# MM_2_0_sch.net
KiCad netlist of a schematic drawn in Altium Designer
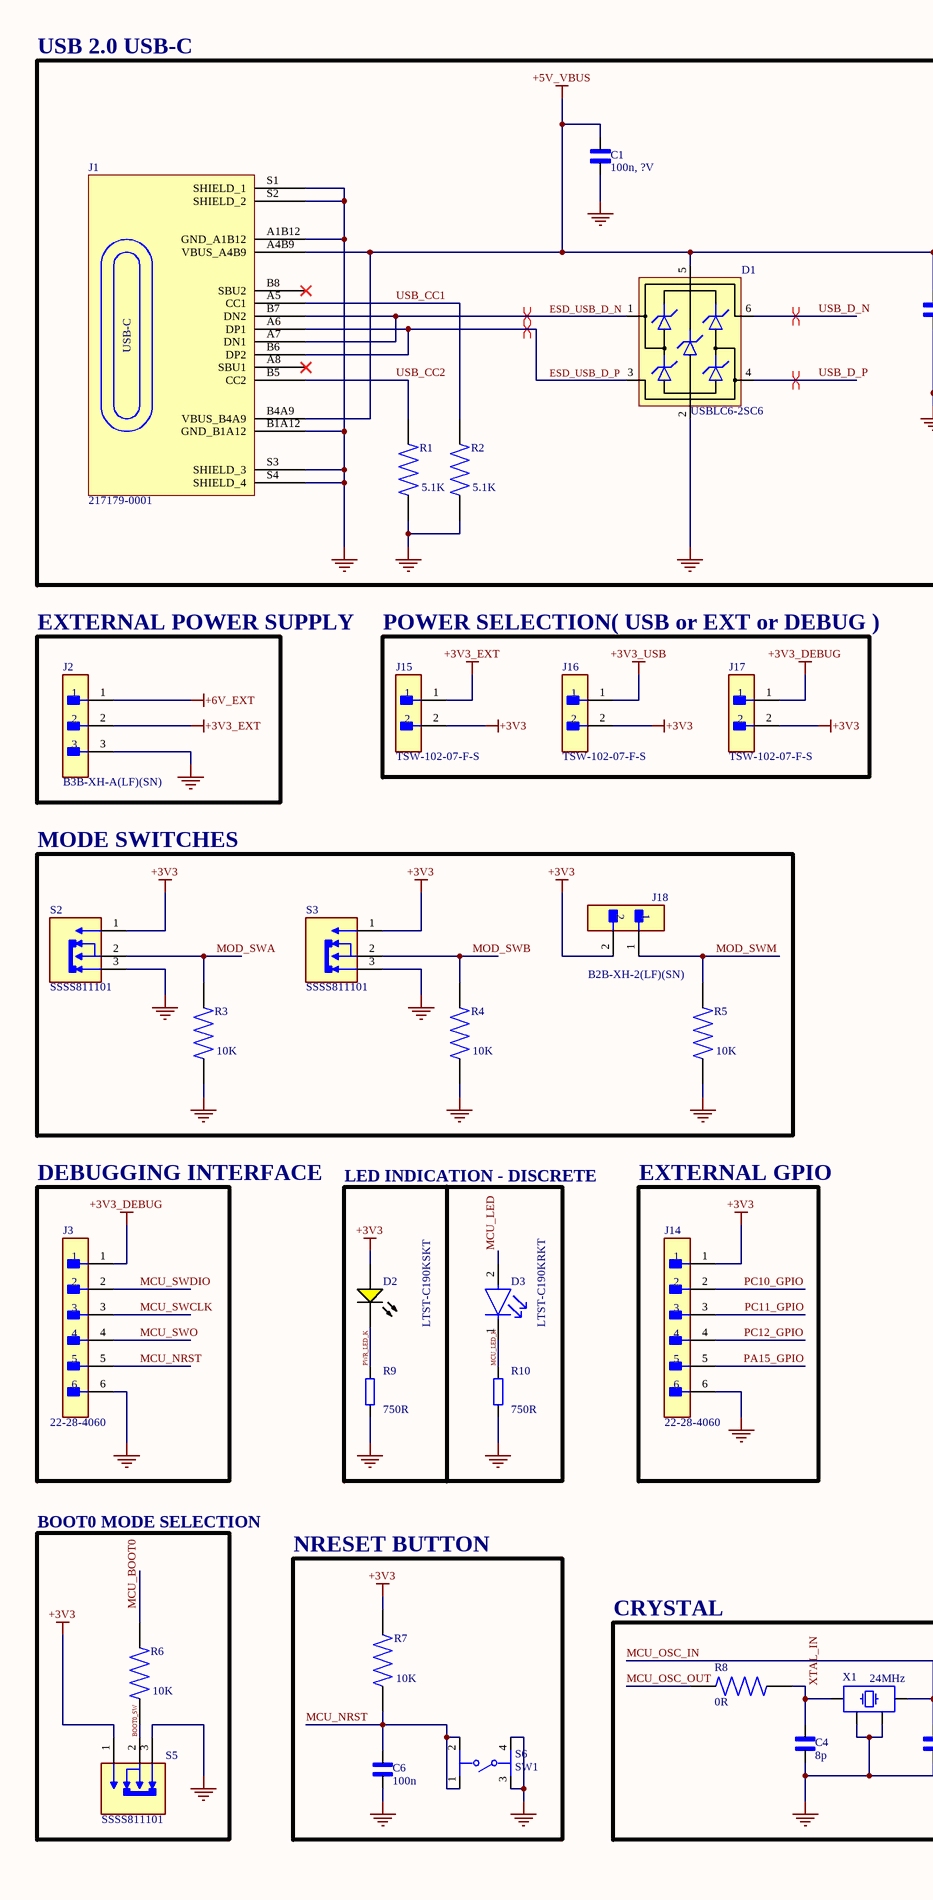
[diagram p0: MM_2.0_sch.SchDoc, left]
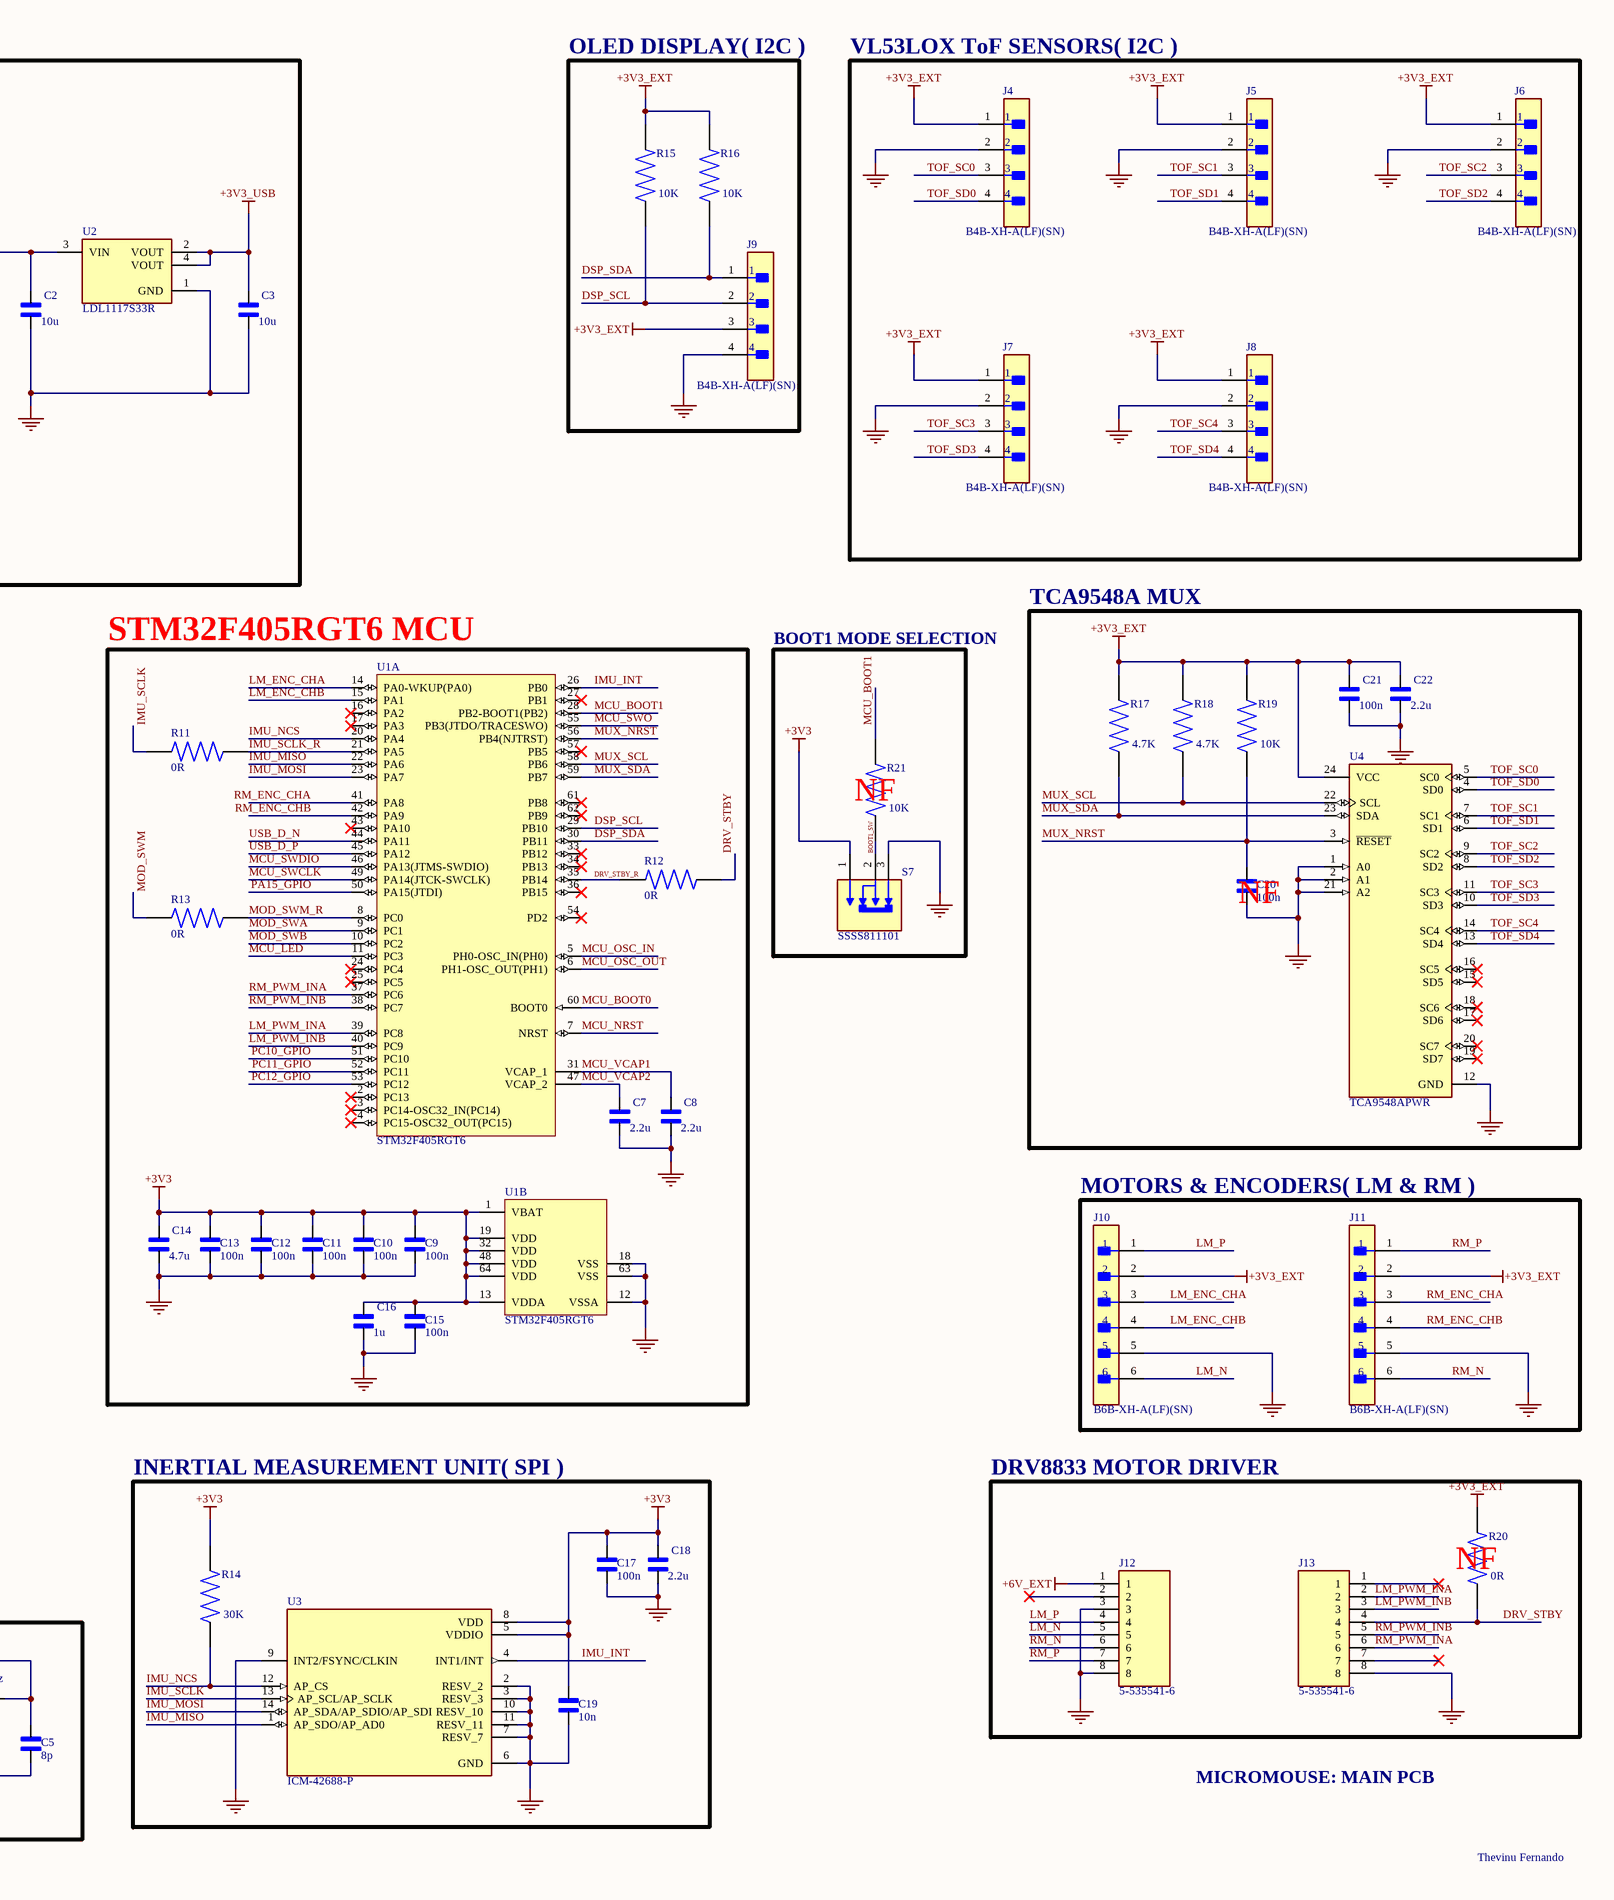
[diagram p1: MM_2.0_sch.SchDoc, right]

(export (version "E")
  (design (tool "Eeschema 10.0.6"))
  (components
    (comp (ref "C1")
      (value "100n, ?V")
      (footprint "CAP_0402")
      (description "0.1 ÂµF Â±10% 16V Ceramic Capacitor X7R 0402 (1005 Metric)")
      (fields (field (name "MF") "Samsung") (field (name "MP") "CL05B104KO5NNNC"))
      (libsource (lib "MM_2.0_schlib") (part "CL05B104KO5NNNC"))
    )
    (comp (ref "C2")
      (value "10u")
      (footprint "CAPC2012X140N")
      (description "10 ÂµF Â±10% 16V Ceramic Capacitor X7R 0805 (2012 Metric)")
      (fields (field (name "MF") "Samsung Electro-Mechanics") (field (name "MP") "CL21B106KOQNNNE"))
      (libsource (lib "MM_2.0_schlib") (part "CL21B106KOQNNNE"))
    )
    (comp (ref "C3")
      (value "10u")
      (footprint "CAPC2012X140N")
      (description "10 ÂµF Â±10% 16V Ceramic Capacitor X7R 0805 (2012 Metric)")
      (fields (field (name "MF") "Samsung Electro-Mechanics") (field (name "MP") "CL21B106KOQNNNE"))
      (libsource (lib "MM_2.0_schlib") (part "CL21B106KOQNNNE"))
    )
    (comp (ref "C4")
      (value "8p")
      (footprint "CAP_0402")
      (description "0.1 ÂµF Â±10% 16V Ceramic Capacitor X7R 0402 (1005 Metric)")
      (fields (field (name "MF") "Samsung") (field (name "MP") "CL05B104KO5NNNC"))
      (libsource (lib "MM_2.0_schlib") (part "CL05B104KO5NNNC"))
    )
    (comp (ref "C5")
      (value "8p")
      (footprint "CAP_0402")
      (description "0.1 ÂµF Â±10% 16V Ceramic Capacitor X7R 0402 (1005 Metric)")
      (fields (field (name "MF") "Samsung") (field (name "MP") "CL05B104KO5NNNC"))
      (libsource (lib "MM_2.0_schlib") (part "CL05B104KO5NNNC"))
    )
    (comp (ref "C6")
      (value "100n")
      (footprint "CAP_0402")
      (description "0.1 ÂµF Â±10% 16V Ceramic Capacitor X7R 0402 (1005 Metric)")
      (fields (field (name "MF") "Samsung") (field (name "MP") "CL05B104KO5NNNC"))
      (libsource (lib "MM_2.0_schlib") (part "CL05B104KO5NNNC"))
    )
    (comp (ref "C7")
      (value "2.2u")
      (footprint "CL10A105KO8NNNC 4.7u 16V 603")
      (description "4.7 ÂµF Â±10% 16V Ceramic Capacitor X5R 0603 (1608 Metric)")
      (fields (field (name "MF") "Samsung Electro-Mechanics") (field (name "MP") "CL10A475KO8NNNC"))
      (libsource (lib "MM_2.0_schlib") (part "CL10A475KO8NNNC"))
    )
    (comp (ref "C8")
      (value "2.2u")
      (footprint "CL10A105KO8NNNC 4.7u 16V 603")
      (description "4.7 ÂµF Â±10% 16V Ceramic Capacitor X5R 0603 (1608 Metric)")
      (fields (field (name "MF") "Samsung Electro-Mechanics") (field (name "MP") "CL10A475KO8NNNC"))
      (libsource (lib "MM_2.0_schlib") (part "CL10A475KO8NNNC"))
    )
    (comp (ref "C9")
      (value "100n")
      (footprint "CAP_0402")
      (description "0.1 ÂµF Â±10% 16V Ceramic Capacitor X7R 0402 (1005 Metric)")
      (fields (field (name "MF") "Samsung") (field (name "MP") "CL05B104KO5NNNC"))
      (libsource (lib "MM_2.0_schlib") (part "CL05B104KO5NNNC"))
    )
    (comp (ref "C10")
      (value "100n")
      (footprint "CAP_0402")
      (description "0.1 ÂµF Â±10% 16V Ceramic Capacitor X7R 0402 (1005 Metric)")
      (fields (field (name "MF") "Samsung") (field (name "MP") "CL05B104KO5NNNC"))
      (libsource (lib "MM_2.0_schlib") (part "CL05B104KO5NNNC"))
    )
    (comp (ref "C11")
      (value "100n")
      (footprint "CAP_0402")
      (description "0.1 ÂµF Â±10% 16V Ceramic Capacitor X7R 0402 (1005 Metric)")
      (fields (field (name "MF") "Samsung") (field (name "MP") "CL05B104KO5NNNC"))
      (libsource (lib "MM_2.0_schlib") (part "CL05B104KO5NNNC"))
    )
    (comp (ref "C12")
      (value "100n")
      (footprint "CAP_0402")
      (description "0.1 ÂµF Â±10% 16V Ceramic Capacitor X7R 0402 (1005 Metric)")
      (fields (field (name "MF") "Samsung") (field (name "MP") "CL05B104KO5NNNC"))
      (libsource (lib "MM_2.0_schlib") (part "CL05B104KO5NNNC"))
    )
    (comp (ref "C13")
      (value "100n")
      (footprint "CAP_0402")
      (description "0.1 ÂµF Â±10% 16V Ceramic Capacitor X7R 0402 (1005 Metric)")
      (fields (field (name "MF") "Samsung") (field (name "MP") "CL05B104KO5NNNC"))
      (libsource (lib "MM_2.0_schlib") (part "CL05B104KO5NNNC"))
    )
    (comp (ref "C14")
      (value "4.7u")
      (footprint "CL10A105KO8NNNC 4.7u 16V 603")
      (description "4.7 ÂµF Â±10% 16V Ceramic Capacitor X5R 0603 (1608 Metric)")
      (fields (field (name "MF") "Samsung Electro-Mechanics") (field (name "MP") "CL10A475KO8NNNC"))
      (libsource (lib "MM_2.0_schlib") (part "CL10A475KO8NNNC"))
    )
    (comp (ref "C15")
      (value "100n")
      (footprint "CAP_0402")
      (description "0.1 ÂµF Â±10% 16V Ceramic Capacitor X7R 0402 (1005 Metric)")
      (fields (field (name "MF") "Samsung") (field (name "MP") "CL05B104KO5NNNC"))
      (libsource (lib "MM_2.0_schlib") (part "CL05B104KO5NNNC"))
    )
    (comp (ref "C16")
      (value "1u")
      (footprint "CL10A105KO8NNNC 1u 16V 603")
      (description "1uF; 16V; X5R; MLCC; Â±10%; SMD; Capacitor: ceramic; 0603; -55Ã·85Â°C")
      (fields (field (name "MF") "Samsung Electro-Mechanics") (field (name "MP") "CL10A105KO8NNNC"))
      (libsource (lib "MM_2.0_schlib") (part "CL10A105KO8NNNC"))
    )
    (comp (ref "C17")
      (value "100n")
      (footprint "CAP_0402")
      (description "0.1 ÂµF Â±10% 16V Ceramic Capacitor X7R 0402 (1005 Metric)")
      (fields (field (name "MF") "Samsung") (field (name "MP") "CL05B104KO5NNNC"))
      (libsource (lib "MM_2.0_schlib") (part "CL05B104KO5NNNC"))
    )
    (comp (ref "C18")
      (value "2.2u")
      (footprint "CL10A105KO8NNNC 4.7u 16V 603")
      (description "4.7 ÂµF Â±10% 16V Ceramic Capacitor X5R 0603 (1608 Metric)")
      (fields (field (name "MF") "Samsung Electro-Mechanics") (field (name "MP") "CL10A475KO8NNNC"))
      (libsource (lib "MM_2.0_schlib") (part "CL10A475KO8NNNC"))
    )
    (comp (ref "C19")
      (value "10n")
      (footprint "CAP_0402")
      (description "0.1 ÂµF Â±10% 16V Ceramic Capacitor X7R 0402 (1005 Metric)")
      (fields (field (name "MF") "Samsung") (field (name "MP") "CL05B104KO5NNNC"))
      (libsource (lib "MM_2.0_schlib") (part "CL05B104KO5NNNC"))
    )
    (comp (ref "C20")
      (value "100n")
      (footprint "CAP_0402")
      (description "0.1 ÂµF Â±10% 16V Ceramic Capacitor X7R 0402 (1005 Metric)")
      (fields (field (name "MF") "Samsung") (field (name "MP") "CL05B104KO5NNNC"))
      (libsource (lib "MM_2.0_schlib") (part "CL05B104KO5NNNC"))
    )
    (comp (ref "C21")
      (value "100n")
      (footprint "CAP_0402")
      (description "0.1 ÂµF Â±10% 16V Ceramic Capacitor X7R 0402 (1005 Metric)")
      (fields (field (name "MF") "Samsung") (field (name "MP") "CL05B104KO5NNNC"))
      (libsource (lib "MM_2.0_schlib") (part "CL05B104KO5NNNC"))
    )
    (comp (ref "C22")
      (value "2.2u")
      (footprint "CL10A105KO8NNNC 4.7u 16V 603")
      (description "4.7 ÂµF Â±10% 16V Ceramic Capacitor X5R 0603 (1608 Metric)")
      (fields (field (name "MF") "Samsung Electro-Mechanics") (field (name "MP") "CL10A475KO8NNNC"))
      (libsource (lib "MM_2.0_schlib") (part "CL10A475KO8NNNC"))
    )
    (comp (ref "D1")
      (value "USBLC6-2SC6")
      (footprint "SOT95P280X145-6N")
      (description "Low-Capacitance ESD Protection USB")
      (fields (field (name "MANUFACTURER") "STMicroelectronics"))
      (libsource (lib "MM_2.0_schlib") (part "USBLC6-2SC6"))
    )
    (comp (ref "D2")
      (value "LTST-C190KSKT")
      (footprint "LTST-C190KSKT_V")
      (description "LED Uni-Color Yellow, 75 mW, 30 mA, -30 to 85 degC, 2-Pin SMD, RoHS, Tape and Reel")
      (fields (field (name "TOLERANCE") "1%"))
      (libsource (lib "MM_2.0_schlib") (part "CMP-1674-00009-1"))
    )
    (comp (ref "D3")
      (value "LTST-C190KRKT")
      (footprint "FP-LTST-C190KRKT-MFG")
      (description "LED RED CLEAR CHIP SMD")
      (libsource (lib "MM_2.0_schlib") (part "CMP-1674-00011-2"))
    )
    (comp (ref "J1")
      (value "217179-0001")
      (footprint "FP-2171790001-MFG USB-C 2.0")
      (description "CONN RCP USB2.0 TYP C 24P SMD RA")
      (fields (field (name "MANUFACTURER") "Molex") (field (name "LCSC PART NUMBER") "C3197684"))
      (libsource (lib "MM_2.0_schlib") (part "217179-0001"))
    )
    (comp (ref "J2")
      (value "B3B-XH-A(LF)(SN)")
      (footprint "FP-B3B-XH-A_LF_SN-MFG")
      (description "CONN HEADER VERT 3POS 2.5MM")
      (libsource (lib "MM_2.0_schlib") (part "CMP-17439-000014-3"))
    )
    (comp (ref "J3")
      (value "22-28-4060")
      (footprint "FP-22-28-4060-MFG")
      (description "CONN HEADER VERT 6POS 2.54MM")
      (libsource (lib "MM_2.0_schlib") (part "f2cb566baf1c37ab5a3b8e90bbeafd6"))
    )
    (comp (ref "J4")
      (value "B4B-XH-A(LF)(SN)")
      (footprint "FP-B4B-XH-A_LF_SN-MFG")
      (description "CONN HEADER VERT 4POS 2.5MM")
      (libsource (lib "MM_2.0_schlib") (part "CMP-17439-000250-1"))
    )
    (comp (ref "J5")
      (value "B4B-XH-A(LF)(SN)")
      (footprint "FP-B4B-XH-A_LF_SN-MFG")
      (description "CONN HEADER VERT 4POS 2.5MM")
      (libsource (lib "MM_2.0_schlib") (part "CMP-17439-000250-1"))
    )
    (comp (ref "J6")
      (value "B4B-XH-A(LF)(SN)")
      (footprint "FP-B4B-XH-A_LF_SN-MFG")
      (description "CONN HEADER VERT 4POS 2.5MM")
      (libsource (lib "MM_2.0_schlib") (part "CMP-17439-000250-1"))
    )
    (comp (ref "J7")
      (value "B4B-XH-A(LF)(SN)")
      (footprint "FP-B4B-XH-A_LF_SN-MFG")
      (description "CONN HEADER VERT 4POS 2.5MM")
      (libsource (lib "MM_2.0_schlib") (part "CMP-17439-000250-1"))
    )
    (comp (ref "J8")
      (value "B4B-XH-A(LF)(SN)")
      (footprint "FP-B4B-XH-A_LF_SN-MFG")
      (description "CONN HEADER VERT 4POS 2.5MM")
      (libsource (lib "MM_2.0_schlib") (part "CMP-17439-000250-1"))
    )
    (comp (ref "J9")
      (value "B4B-XH-A(LF)(SN)")
      (footprint "FP-B4B-XH-A_LF_SN-MFG")
      (description "CONN HEADER VERT 4POS 2.5MM")
      (libsource (lib "MM_2.0_schlib") (part "CMP-17439-000250-1"))
    )
    (comp (ref "J10")
      (value "B6B-XH-A(LF)(SN)")
      (footprint "FP-B6B-XH-A_LF_SN-MFG")
      (description "CONN HEADER VERT 6POS 2.5MM")
      (libsource (lib "MM_2.0_schlib") (part "CMP-17439-000076-1"))
    )
    (comp (ref "J11")
      (value "B6B-XH-A(LF)(SN)")
      (footprint "FP-B6B-XH-A_LF_SN-MFG")
      (description "CONN HEADER VERT 6POS 2.5MM")
      (libsource (lib "MM_2.0_schlib") (part "CMP-17439-000076-1"))
    )
    (comp (ref "J12")
      (value "5-535541-6")
      (footprint "TE_5-535541-6")
      (fields (field (name "MF") "TE Connectivity"))
      (libsource (lib "") (part "5-535541-6_1"))
    )
    (comp (ref "J13")
      (value "5-535541-6")
      (footprint "TE_5-535541-6")
      (fields (field (name "MF") "TE Connectivity"))
      (libsource (lib "MM_2.0_schlib") (part "5-535541-6"))
    )
    (comp (ref "J14")
      (value "22-28-4060")
      (footprint "FP-22-28-4060-MFG")
      (description "CONN HEADER VERT 6POS 2.54MM")
      (libsource (lib "MM_2.0_schlib") (part "f2cb566baf1c37ab5a3b8e90bbeafd6"))
    )
    (comp (ref "J15")
      (value "TSW-102-07-F-S")
      (footprint "FP-TSW-102-07-F-S-MFG")
      (description "CONN HEADER VERT 2POS 2.54MM")
      (libsource (lib "MM_2.0_schlib") (part "CMP-02766-001458-1"))
    )
    (comp (ref "J16")
      (value "TSW-102-07-F-S")
      (footprint "FP-TSW-102-07-F-S-MFG")
      (description "CONN HEADER VERT 2POS 2.54MM")
      (libsource (lib "MM_2.0_schlib") (part "CMP-02766-001458-1"))
    )
    (comp (ref "J17")
      (value "TSW-102-07-F-S")
      (footprint "FP-TSW-102-07-F-S-MFG")
      (description "CONN HEADER VERT 2POS 2.54MM")
      (libsource (lib "MM_2.0_schlib") (part "CMP-02766-001458-1"))
    )
    (comp (ref "J18")
      (value "B2B-XH-2(LF)(SN)")
      (footprint "FP-B2B-XH-2_LF_SN-MFG")
      (description "CONN HEADER VERT 2POS 2.5MM")
      (libsource (lib "MM_2.0_schlib") (part "CMP-17439-000499-1"))
    )
    (comp (ref "R1")
      (value "5.1K")
      (footprint "RES_ERJ2RKF1002X 100K 100mW 402")
      (description "10 kOhms 1% 0.1W, 1/10W Chip Resistor 0402 (1005 Metric) Automotive AEC-Q200 Thick Film")
      (fields (field (name "MF") "Panasonic") (field (name "MP") "ERJ-2RKF1002X"))
      (libsource (lib "MM_2.0_schlib") (part "ERJ2RKF1002X"))
    )
    (comp (ref "R2")
      (value "5.1K")
      (footprint "RES_ERJ2RKF1002X 100K 100mW 402")
      (description "10 kOhms 1% 0.1W, 1/10W Chip Resistor 0402 (1005 Metric) Automotive AEC-Q200 Thick Film")
      (fields (field (name "MF") "Panasonic") (field (name "MP") "ERJ-2RKF1002X"))
      (libsource (lib "MM_2.0_schlib") (part "ERJ2RKF1002X"))
    )
    (comp (ref "R3")
      (value "10K")
      (footprint "RES_ERJ2RKF1002X 100K 100mW 402")
      (description "10 kOhms 1% 0.1W, 1/10W Chip Resistor 0402 (1005 Metric) Automotive AEC-Q200 Thick Film")
      (fields (field (name "MF") "Panasonic") (field (name "MP") "ERJ-2RKF1002X"))
      (libsource (lib "MM_2.0_schlib") (part "ERJ2RKF1002X"))
    )
    (comp (ref "R4")
      (value "10K")
      (footprint "RES_ERJ2RKF1002X 100K 100mW 402")
      (description "10 kOhms 1% 0.1W, 1/10W Chip Resistor 0402 (1005 Metric) Automotive AEC-Q200 Thick Film")
      (fields (field (name "MF") "Panasonic") (field (name "MP") "ERJ-2RKF1002X"))
      (libsource (lib "MM_2.0_schlib") (part "ERJ2RKF1002X"))
    )
    (comp (ref "R5")
      (value "10K")
      (footprint "RES_ERJ2RKF1002X 100K 100mW 402")
      (description "10 kOhms 1% 0.1W, 1/10W Chip Resistor 0402 (1005 Metric) Automotive AEC-Q200 Thick Film")
      (fields (field (name "MF") "Panasonic") (field (name "MP") "ERJ-2RKF1002X"))
      (libsource (lib "MM_2.0_schlib") (part "ERJ2RKF1002X"))
    )
    (comp (ref "R6")
      (value "10K")
      (footprint "RES_ERJ2RKF1002X 100K 100mW 402")
      (description "10 kOhms 1% 0.1W, 1/10W Chip Resistor 0402 (1005 Metric) Automotive AEC-Q200 Thick Film")
      (fields (field (name "MF") "Panasonic") (field (name "MP") "ERJ-2RKF1002X"))
      (libsource (lib "MM_2.0_schlib") (part "ERJ2RKF1002X"))
    )
    (comp (ref "R7")
      (value "10K")
      (footprint "RES_ERJ2RKF1002X 100K 100mW 402")
      (description "10 kOhms 1% 0.1W, 1/10W Chip Resistor 0402 (1005 Metric) Automotive AEC-Q200 Thick Film")
      (fields (field (name "MF") "Panasonic") (field (name "MP") "ERJ-2RKF1002X"))
      (libsource (lib "MM_2.0_schlib") (part "ERJ2RKF1002X"))
    )
    (comp (ref "R8")
      (value "0R")
      (footprint "RES_ERJ2RKF1002X 100K 100mW 402")
      (description "10 kOhms 1% 0.1W, 1/10W Chip Resistor 0402 (1005 Metric) Automotive AEC-Q200 Thick Film")
      (fields (field (name "MF") "Panasonic") (field (name "MP") "ERJ-2RKF1002X"))
      (libsource (lib "MM_2.0_schlib") (part "ERJ2RKF1002X"))
    )
    (comp (ref "R9")
      (value "750R")
      (footprint "RES_0603")
      (description "Resistor SMD 0603")
      (libsource (lib "MM_2.0_schlib") (part "RES_0603"))
    )
    (comp (ref "R10")
      (value "750R")
      (footprint "RES_0603")
      (description "Resistor SMD 0603")
      (libsource (lib "MM_2.0_schlib") (part "RES_0603"))
    )
    (comp (ref "R11")
      (value "0R")
      (footprint "RES_ERJ2RKF1002X 100K 100mW 402")
      (description "10 kOhms 1% 0.1W, 1/10W Chip Resistor 0402 (1005 Metric) Automotive AEC-Q200 Thick Film")
      (fields (field (name "MF") "Panasonic") (field (name "MP") "ERJ-2RKF1002X"))
      (libsource (lib "MM_2.0_schlib") (part "ERJ2RKF1002X"))
    )
    (comp (ref "R12")
      (value "0R")
      (footprint "RES_ERJ2RKF1002X 100K 100mW 402")
      (description "10 kOhms 1% 0.1W, 1/10W Chip Resistor 0402 (1005 Metric) Automotive AEC-Q200 Thick Film")
      (fields (field (name "MF") "Panasonic") (field (name "MP") "ERJ-2RKF1002X"))
      (libsource (lib "MM_2.0_schlib") (part "ERJ2RKF1002X"))
    )
    (comp (ref "R13")
      (value "0R")
      (footprint "RES_ERJ2RKF1002X 100K 100mW 402")
      (description "10 kOhms 1% 0.1W, 1/10W Chip Resistor 0402 (1005 Metric) Automotive AEC-Q200 Thick Film")
      (fields (field (name "MF") "Panasonic") (field (name "MP") "ERJ-2RKF1002X"))
      (libsource (lib "MM_2.0_schlib") (part "ERJ2RKF1002X"))
    )
    (comp (ref "R14")
      (value "30K")
      (footprint "RES_ERJ2RKF1002X 100K 100mW 402")
      (description "10 kOhms 1% 0.1W, 1/10W Chip Resistor 0402 (1005 Metric) Automotive AEC-Q200 Thick Film")
      (fields (field (name "MF") "Panasonic") (field (name "MP") "ERJ-2RKF1002X"))
      (libsource (lib "MM_2.0_schlib") (part "ERJ2RKF1002X"))
    )
    (comp (ref "R15")
      (value "10K")
      (footprint "RES_ERJ2RKF1002X 100K 100mW 402")
      (description "10 kOhms 1% 0.1W, 1/10W Chip Resistor 0402 (1005 Metric) Automotive AEC-Q200 Thick Film")
      (fields (field (name "MF") "Panasonic") (field (name "MP") "ERJ-2RKF1002X"))
      (libsource (lib "MM_2.0_schlib") (part "ERJ2RKF1002X"))
    )
    (comp (ref "R16")
      (value "10K")
      (footprint "RES_ERJ2RKF1002X 100K 100mW 402")
      (description "10 kOhms 1% 0.1W, 1/10W Chip Resistor 0402 (1005 Metric) Automotive AEC-Q200 Thick Film")
      (fields (field (name "MF") "Panasonic") (field (name "MP") "ERJ-2RKF1002X"))
      (libsource (lib "MM_2.0_schlib") (part "ERJ2RKF1002X"))
    )
    (comp (ref "R17")
      (value "4.7K")
      (footprint "RES_ERJ2RKF1002X 100K 100mW 402")
      (description "10 kOhms 1% 0.1W, 1/10W Chip Resistor 0402 (1005 Metric) Automotive AEC-Q200 Thick Film")
      (fields (field (name "MF") "Panasonic") (field (name "MP") "ERJ-2RKF1002X"))
      (libsource (lib "MM_2.0_schlib") (part "ERJ2RKF1002X"))
    )
    (comp (ref "R18")
      (value "4.7K")
      (footprint "RES_ERJ2RKF1002X 100K 100mW 402")
      (description "10 kOhms 1% 0.1W, 1/10W Chip Resistor 0402 (1005 Metric) Automotive AEC-Q200 Thick Film")
      (fields (field (name "MF") "Panasonic") (field (name "MP") "ERJ-2RKF1002X"))
      (libsource (lib "MM_2.0_schlib") (part "ERJ2RKF1002X"))
    )
    (comp (ref "R19")
      (value "10K")
      (footprint "RES_ERJ2RKF1002X 100K 100mW 402")
      (description "10 kOhms 1% 0.1W, 1/10W Chip Resistor 0402 (1005 Metric) Automotive AEC-Q200 Thick Film")
      (fields (field (name "MF") "Panasonic") (field (name "MP") "ERJ-2RKF1002X"))
      (libsource (lib "MM_2.0_schlib") (part "ERJ2RKF1002X"))
    )
    (comp (ref "R20")
      (value "0R")
      (footprint "RES_ERJ2RKF1002X 100K 100mW 402")
      (description "10 kOhms 1% 0.1W, 1/10W Chip Resistor 0402 (1005 Metric) Automotive AEC-Q200 Thick Film")
      (fields (field (name "MF") "Panasonic") (field (name "MP") "ERJ-2RKF1002X"))
      (libsource (lib "MM_2.0_schlib") (part "ERJ2RKF1002X"))
    )
    (comp (ref "R21")
      (value "10K")
      (footprint "RES_ERJ2RKF1002X 100K 100mW 402")
      (description "10 kOhms 1% 0.1W, 1/10W Chip Resistor 0402 (1005 Metric) Automotive AEC-Q200 Thick Film")
      (fields (field (name "MF") "Panasonic") (field (name "MP") "ERJ-2RKF1002X"))
      (libsource (lib "MM_2.0_schlib") (part "ERJ2RKF1002X"))
    )
    (comp (ref "S2")
      (value "SSSS811101")
      (footprint "SW_SSSS811101")
      (description "Switch Slide SP Side Slide 0.3A 5VDC 10000Cycles Gull Wing SMD T/R")
      (fields (field (name "MF") "ALPS"))
      (libsource (lib "MM_2.0_schlib") (part "SSSS811101"))
    )
    (comp (ref "S3")
      (value "SSSS811101")
      (footprint "SW_SSSS811101")
      (description "Switch Slide SP Side Slide 0.3A 5VDC 10000Cycles Gull Wing SMD T/R")
      (fields (field (name "MF") "ALPS"))
      (libsource (lib "MM_2.0_schlib") (part "SSSS811101"))
    )
    (comp (ref "S5")
      (value "SSSS811101")
      (footprint "SW_SSSS811101")
      (description "Switch Slide SP Side Slide 0.3A 5VDC 10000Cycles Gull Wing SMD T/R")
      (fields (field (name "MF") "ALPS"))
      (libsource (lib "") (part "SSSS811101_1"))
    )
    (comp (ref "S6")
      (value "SW1")
      (footprint "FP-PTS645SM43SMTR92LFS-MFG")
      (description "SWITCH TACTILE SPST-NO 0.05A 12V")
      (libsource (lib "MM_2.0_schlib") (part "PTS645SM43SMTR92LFS"))
    )
    (comp (ref "S7")
      (value "SSSS811101")
      (footprint "SW_SSSS811101")
      (description "Switch Slide SP Side Slide 0.3A 5VDC 10000Cycles Gull Wing SMD T/R")
      (fields (field (name "MF") "ALPS"))
      (libsource (lib "") (part "SSSS811101_1"))
    )
    (comp (ref "U1")
      (value "STM32F405RGT6")
      (footprint "STM-LQFP64_L")
      (fields (field (name "MANUFACTURER") "STMicroelectronics"))
      (libsource (lib "Altium Content Vault") (part "MC-ARM-STM32F4X5-SQ64"))
    )
    (comp (ref "U2")
      (value "LDL1117S33R")
      (footprint "FP-SOT223-0046067-IPC_A")
      (description "IC REG LINEAR 3.3V 1.2A SOT223")
      (fields
        (field (name "OCTOPART") "https://octopart.com/ldl1117s33r-stmicroelectronics-81876163")
        (field (name "MANUFACTURER") "STMicroelectronics")
      )
      (libsource (lib "MM_2.0_schlib") (part "CMP-12153-000006-1"))
    )
    (comp (ref "U3")
      (value "ICM-42688-P")
      (footprint "PQFN50P300X250X97-14N")
      (description "Accelerometer, Gyroscope, 6 Axis Sensor Output")
      (libsource (lib "MM_2.0_schlib") (part "ICM-42688-P"))
    )
    (comp (ref "U4")
      (value "TCA9548APWR")
      (footprint "FP-PW0024A-IPC_A")
      (description "IC I2C SW 8CH W/RESET 24TSSOP")
      (fields
        (field (name "MANUFACTURER") "Texas Instruments")
        (field (name "OCTOPART") "https://octopart.com/tca9548apwr-texas+instruments-22266789")
      )
      (libsource (lib "MM_2.0_schlib") (part "CMP-04892-000002-1"))
    )
    (comp (ref "X1")
      (value "24MHz")
      (footprint "XTAL_3225")
      (description "Crystal SMD 24MHz 10PPM 7pF 3225")
      (fields
        (field (name "MANUFACTURER") "Epson")
        (field (name "MANUFACTURER PART NUMBER") "TSX-3225 24.0000MF15X-AC")
      )
      (libsource (lib "MM_2.0_schlib") (part "TSX-3225_24.0000MF15X-AC"))
    )
  )
  (nets
    (net (code "1") (name "+3V3") (class "Default")
      (node (ref "C10") (pin "2") (pinfunction "2_2") (pintype "passive"))
      (node (ref "C11") (pin "2") (pinfunction "2_2") (pintype "passive"))
      (node (ref "C12") (pin "2") (pinfunction "2_2") (pintype "passive"))
      (node (ref "C13") (pin "2") (pinfunction "2_2") (pintype "passive"))
      (node (ref "C14") (pin "1") (pinfunction "1_1") (pintype "passive"))
      (node (ref "C15") (pin "2") (pinfunction "2_2") (pintype "passive"))
      (node (ref "C16") (pin "1") (pinfunction "1_1") (pintype "passive"))
      (node (ref "C17") (pin "2") (pinfunction "2_2") (pintype "passive"))
      (node (ref "C18") (pin "1") (pinfunction "1_1") (pintype "passive"))
      (node (ref "C19") (pin "2") (pinfunction "2_2") (pintype "passive"))
      (node (ref "C9") (pin "2") (pinfunction "2_2") (pintype "passive"))
      (node (ref "D2") (pin "1") (pinfunction "A_1") (pintype "passive"))
      (node (ref "J14") (pin "1") (pinfunction "1_1") (pintype "passive"))
      (node (ref "J15") (pin "2") (pinfunction "2_2") (pintype "passive"))
      (node (ref "J16") (pin "2") (pinfunction "2_2") (pintype "passive"))
      (node (ref "J17") (pin "2") (pinfunction "2_2") (pintype "passive"))
      (node (ref "J18") (pin "2") (pinfunction "2_2") (pintype "passive"))
      (node (ref "R14") (pin "2") (pinfunction "2_2") (pintype "passive"))
      (node (ref "R7") (pin "2") (pinfunction "2_2") (pintype "passive"))
      (node (ref "S2") (pin "1") (pinfunction "1_1") (pintype "passive"))
      (node (ref "S3") (pin "1") (pinfunction "1_1") (pintype "passive"))
      (node (ref "S5") (pin "1") (pinfunction "1_1") (pintype "passive"))
      (node (ref "S7") (pin "1") (pinfunction "1_1") (pintype "passive"))
      (node (ref "U1") (pin "1") (pinfunction "VBAT_1") (pintype "power_in"))
      (node (ref "U1") (pin "13") (pinfunction "VDDA_13") (pintype "power_in"))
      (node (ref "U1") (pin "19") (pinfunction "VDD_19") (pintype "power_in"))
      (node (ref "U1") (pin "32") (pinfunction "VDD_32") (pintype "power_in"))
      (node (ref "U1") (pin "48") (pinfunction "VDD_48") (pintype "power_in"))
      (node (ref "U1") (pin "64") (pinfunction "VDD_64") (pintype "power_in"))
      (node (ref "U3") (pin "5") (pinfunction "VDDIO_5") (pintype "power_in"))
      (node (ref "U3") (pin "8") (pinfunction "VDD_8") (pintype "power_in"))
    )
    (net (code "2") (name "+3V3_DEBUG") (class "Default")
      (node (ref "J17") (pin "1") (pinfunction "1_1") (pintype "passive"))
      (node (ref "J3") (pin "1") (pinfunction "1_1") (pintype "passive"))
    )
    (net (code "3") (name "+3V3_EXT") (class "Default")
      (node (ref "C21") (pin "2") (pinfunction "2_2") (pintype "passive"))
      (node (ref "C22") (pin "1") (pinfunction "1_1") (pintype "passive"))
      (node (ref "J10") (pin "2") (pinfunction "2_2") (pintype "passive"))
      (node (ref "J11") (pin "2") (pinfunction "2_2") (pintype "passive"))
      (node (ref "J15") (pin "1") (pinfunction "1_1") (pintype "passive"))
      (node (ref "J2") (pin "2") (pinfunction "2_2") (pintype "passive"))
      (node (ref "J4") (pin "1") (pinfunction "1_1") (pintype "passive"))
      (node (ref "J5") (pin "1") (pinfunction "1_1") (pintype "passive"))
      (node (ref "J6") (pin "1") (pinfunction "1_1") (pintype "passive"))
      (node (ref "J7") (pin "1") (pinfunction "1_1") (pintype "passive"))
      (node (ref "J8") (pin "1") (pinfunction "1_1") (pintype "passive"))
      (node (ref "J9") (pin "3") (pinfunction "3_3") (pintype "passive"))
      (node (ref "R15") (pin "2") (pinfunction "2_2") (pintype "passive"))
      (node (ref "R16") (pin "2") (pinfunction "2_2") (pintype "passive"))
      (node (ref "R17") (pin "2") (pinfunction "2_2") (pintype "passive"))
      (node (ref "R18") (pin "2") (pinfunction "2_2") (pintype "passive"))
      (node (ref "R19") (pin "2") (pinfunction "2_2") (pintype "passive"))
      (node (ref "R20") (pin "2") (pinfunction "2_2") (pintype "passive"))
      (node (ref "U4") (pin "24") (pinfunction "VCC_24") (pintype "power_in"))
    )
    (net (code "4") (name "+3V3_USB") (class "Default")
      (node (ref "C3") (pin "1") (pinfunction "1_1") (pintype "passive"))
      (node (ref "J16") (pin "1") (pinfunction "1_1") (pintype "passive"))
      (node (ref "U2") (pin "2") (pinfunction "VOUT_2") (pintype "power_in"))
      (node (ref "U2") (pin "4") (pinfunction "VOUT_4") (pintype "power_in"))
    )
    (net (code "5") (name "+5V_VBUS") (class "Default")
      (node (ref "C1") (pin "2") (pinfunction "2_2") (pintype "passive"))
      (node (ref "C2") (pin "1") (pinfunction "1_1") (pintype "passive"))
      (node (ref "D1") (pin "5") (pinfunction "VBUS_5") (pintype "power_in"))
      (node (ref "J1") (pin "A4B9") (pinfunction "VBUS_A4B9_A4B9") (pintype "passive"))
      (node (ref "J1") (pin "B4A9") (pinfunction "VBUS_B4A9_B4A9") (pintype "passive"))
      (node (ref "U2") (pin "3") (pinfunction "VIN_3") (pintype "power_in"))
    )
    (net (code "6") (name "+6V_EXT") (class "Default")
      (node (ref "J12") (pin "1") (pinfunction "1_1") (pintype "passive"))
      (node (ref "J2") (pin "1") (pinfunction "1_1") (pintype "passive"))
    )
    (net (code "8") (name "/BOOT0_SW") (class "Default")
      (node (ref "R6") (pin "1") (pinfunction "1_1") (pintype "passive"))
      (node (ref "S5") (pin "2") (pinfunction "2_2") (pintype "passive"))
    )
    (net (code "9") (name "/BOOT1_SW") (class "Default")
      (node (ref "R21") (pin "1") (pinfunction "1_1") (pintype "passive"))
      (node (ref "S7") (pin "2") (pinfunction "2_2") (pintype "passive"))
    )
    (net (code "10") (name "/DRV_STBY") (class "Default")
      (node (ref "J13") (pin "4") (pinfunction "4_4") (pintype "passive"))
      (node (ref "R12") (pin "2") (pinfunction "2_2") (pintype "passive"))
      (node (ref "R20") (pin "1") (pinfunction "1_1") (pintype "passive"))
    )
    (net (code "11") (name "/DRV_STBY_R") (class "Default")
      (node (ref "R12") (pin "1") (pinfunction "1_1") (pintype "passive"))
      (node (ref "U1") (pin "35") (pinfunction "PB14_35") (pintype "bidirectional"))
    )
    (net (code "12") (name "/DSP_SCL") (class "Default")
      (node (ref "J9") (pin "2") (pinfunction "2_2") (pintype "passive"))
      (node (ref "R15") (pin "1") (pinfunction "1_1") (pintype "passive"))
      (node (ref "U1") (pin "29") (pinfunction "PB10_29") (pintype "bidirectional"))
    )
    (net (code "13") (name "/DSP_SDA") (class "Default")
      (node (ref "J9") (pin "1") (pinfunction "1_1") (pintype "passive"))
      (node (ref "R16") (pin "1") (pinfunction "1_1") (pintype "passive"))
      (node (ref "U1") (pin "30") (pinfunction "PB11_30") (pintype "bidirectional"))
    )
    (net (code "14") (name "/ESD_USB_D_N") (class "Default")
      (node (ref "D1") (pin "1") (pinfunction "IO1_1") (pintype "bidirectional"))
      (node (ref "J1") (pin "A7") (pinfunction "DN1_A7") (pintype "passive"))
      (node (ref "J1") (pin "B7") (pinfunction "DN2_B7") (pintype "passive"))
    )
    (net (code "15") (name "/ESD_USB_D_P") (class "Default")
      (node (ref "D1") (pin "3") (pinfunction "IO2_3") (pintype "bidirectional"))
      (node (ref "J1") (pin "A6") (pinfunction "DP1_A6") (pintype "passive"))
      (node (ref "J1") (pin "B6") (pinfunction "DP2_B6") (pintype "passive"))
    )
    (net (code "16") (name "/IMU_INT") (class "Default")
      (node (ref "U1") (pin "26") (pinfunction "PB0_26") (pintype "bidirectional"))
      (node (ref "U3") (pin "4") (pinfunction "INT1/INT_4") (pintype "output"))
    )
    (net (code "17") (name "/IMU_MISO") (class "Default")
      (node (ref "U1") (pin "22") (pinfunction "PA6_22") (pintype "bidirectional"))
      (node (ref "U3") (pin "1") (pinfunction "AP_SDO/AP_AD0_1") (pintype "bidirectional"))
    )
    (net (code "18") (name "/IMU_MOSI") (class "Default")
      (node (ref "U1") (pin "23") (pinfunction "PA7_23") (pintype "bidirectional"))
      (node (ref "U3") (pin "14") (pinfunction "AP_SDA/AP_SDIO/AP_SDI_14") (pintype "bidirectional"))
    )
    (net (code "19") (name "/IMU_NCS") (class "Default")
      (node (ref "R14") (pin "1") (pinfunction "1_1") (pintype "passive"))
      (node (ref "U1") (pin "20") (pinfunction "PA4_20") (pintype "bidirectional"))
      (node (ref "U3") (pin "12") (pinfunction "AP_CS_12") (pintype "input"))
    )
    (net (code "20") (name "/IMU_SCLK") (class "Default")
      (node (ref "R11") (pin "1") (pinfunction "1_1") (pintype "passive"))
      (node (ref "U3") (pin "13") (pinfunction "AP_SCL/AP_SCLK_13") (pintype "input"))
    )
    (net (code "21") (name "/IMU_SCLK_R") (class "Default")
      (node (ref "R11") (pin "2") (pinfunction "2_2") (pintype "passive"))
      (node (ref "U1") (pin "21") (pinfunction "PA5_21") (pintype "bidirectional"))
    )
    (net (code "22") (name "/LM_ENC_CHA") (class "Default")
      (node (ref "J10") (pin "3") (pinfunction "3_3") (pintype "passive"))
      (node (ref "U1") (pin "14") (pinfunction "PA0-WKUP(PA0)_14") (pintype "bidirectional"))
    )
    (net (code "23") (name "/LM_ENC_CHB") (class "Default")
      (node (ref "J10") (pin "4") (pinfunction "4_4") (pintype "passive"))
      (node (ref "U1") (pin "15") (pinfunction "PA1_15") (pintype "bidirectional"))
    )
    (net (code "24") (name "/LM_N") (class "Default")
      (node (ref "J10") (pin "6") (pinfunction "6_6") (pintype "passive"))
      (node (ref "J12") (pin "5") (pinfunction "5_5") (pintype "passive"))
    )
    (net (code "25") (name "/LM_P") (class "Default")
      (node (ref "J10") (pin "1") (pinfunction "1_1") (pintype "passive"))
      (node (ref "J12") (pin "4") (pinfunction "4_4") (pintype "passive"))
    )
    (net (code "26") (name "/LM_PWM_INA") (class "Default")
      (node (ref "J13") (pin "2") (pinfunction "2_2") (pintype "passive"))
      (node (ref "U1") (pin "39") (pinfunction "PC8_39") (pintype "bidirectional"))
    )
    (net (code "27") (name "/LM_PWM_INB") (class "Default")
      (node (ref "J13") (pin "3") (pinfunction "3_3") (pintype "passive"))
      (node (ref "U1") (pin "40") (pinfunction "PC9_40") (pintype "bidirectional"))
    )
    (net (code "28") (name "/MCU_BOOT0") (class "Default")
      (node (ref "R6") (pin "2") (pinfunction "2_2") (pintype "passive"))
      (node (ref "U1") (pin "60") (pinfunction "BOOT0_60") (pintype "input"))
    )
    (net (code "29") (name "/MCU_BOOT1") (class "Default")
      (node (ref "R21") (pin "2") (pinfunction "2_2") (pintype "passive"))
      (node (ref "U1") (pin "28") (pinfunction "PB2-BOOT1(PB2)_28") (pintype "bidirectional"))
    )
    (net (code "30") (name "/MCU_LED") (class "Default")
      (node (ref "D3") (pin "2") (pinfunction "A_2") (pintype "passive"))
      (node (ref "U1") (pin "11") (pinfunction "PC3_11") (pintype "bidirectional"))
    )
    (net (code "31") (name "/MCU_LED_K") (class "Default")
      (node (ref "D3") (pin "1") (pinfunction "C_1") (pintype "passive"))
      (node (ref "R10") (pin "2") (pinfunction "2_2") (pintype "passive"))
    )
    (net (code "32") (name "/MCU_NRST") (class "Default")
      (node (ref "C6") (pin "2") (pinfunction "2_2") (pintype "passive"))
      (node (ref "J3") (pin "5") (pinfunction "5_5") (pintype "passive"))
      (node (ref "R7") (pin "1") (pinfunction "1_1") (pintype "passive"))
      (node (ref "S6") (pin "1") (pinfunction "1_1") (pintype "passive"))
      (node (ref "S6") (pin "2") (pinfunction "2_2") (pintype "passive"))
      (node (ref "U1") (pin "7") (pinfunction "NRST_7") (pintype "bidirectional"))
    )
    (net (code "33") (name "/MCU_OSC_IN") (class "Default")
      (node (ref "C5") (pin "2") (pinfunction "2_2") (pintype "passive"))
      (node (ref "U1") (pin "5") (pinfunction "PH0-OSC_IN(PH0)_5") (pintype "bidirectional"))
      (node (ref "X1") (pin "3") (pinfunction "3_3") (pintype "passive"))
    )
    (net (code "34") (name "/MCU_OSC_OUT") (class "Default")
      (node (ref "R8") (pin "1") (pinfunction "1_1") (pintype "passive"))
      (node (ref "U1") (pin "6") (pinfunction "PH1-OSC_OUT(PH1)_6") (pintype "bidirectional"))
    )
    (net (code "35") (name "/MCU_SWCLK") (class "Default")
      (node (ref "J3") (pin "3") (pinfunction "3_3") (pintype "passive"))
      (node (ref "U1") (pin "49") (pinfunction "PA14(JTCK-SWCLK)_49") (pintype "bidirectional"))
    )
    (net (code "36") (name "/MCU_SWDIO") (class "Default")
      (node (ref "J3") (pin "2") (pinfunction "2_2") (pintype "passive"))
      (node (ref "U1") (pin "46") (pinfunction "PA13(JTMS-SWDIO)_46") (pintype "bidirectional"))
    )
    (net (code "37") (name "/MCU_SWO") (class "Default")
      (node (ref "J3") (pin "4") (pinfunction "4_4") (pintype "passive"))
      (node (ref "U1") (pin "55") (pinfunction "PB3(JTDO/TRACESWO)_55") (pintype "bidirectional"))
    )
    (net (code "38") (name "/MCU_VCAP1") (class "Default")
      (node (ref "C8") (pin "1") (pinfunction "1_1") (pintype "passive"))
      (node (ref "U1") (pin "31") (pinfunction "VCAP_1_31") (pintype "power_in"))
    )
    (net (code "39") (name "/MCU_VCAP2") (class "Default")
      (node (ref "C7") (pin "1") (pinfunction "1_1") (pintype "passive"))
      (node (ref "U1") (pin "47") (pinfunction "VCAP_2_47") (pintype "power_in"))
    )
    (net (code "40") (name "/MOD_SWA") (class "Default")
      (node (ref "R3") (pin "2") (pinfunction "2_2") (pintype "passive"))
      (node (ref "S2") (pin "2") (pinfunction "2_2") (pintype "passive"))
      (node (ref "U1") (pin "9") (pinfunction "PC1_9") (pintype "bidirectional"))
    )
    (net (code "41") (name "/MOD_SWB") (class "Default")
      (node (ref "R4") (pin "2") (pinfunction "2_2") (pintype "passive"))
      (node (ref "S3") (pin "2") (pinfunction "2_2") (pintype "passive"))
      (node (ref "U1") (pin "10") (pinfunction "PC2_10") (pintype "bidirectional"))
    )
    (net (code "42") (name "/MOD_SWM") (class "Default")
      (node (ref "J18") (pin "1") (pinfunction "1_1") (pintype "passive"))
      (node (ref "R13") (pin "1") (pinfunction "1_1") (pintype "passive"))
      (node (ref "R5") (pin "2") (pinfunction "2_2") (pintype "passive"))
    )
    (net (code "43") (name "/MOD_SWM_R") (class "Default")
      (node (ref "R13") (pin "2") (pinfunction "2_2") (pintype "passive"))
      (node (ref "U1") (pin "8") (pinfunction "PC0_8") (pintype "bidirectional"))
    )
    (net (code "44") (name "/MUX_NRST") (class "Default")
      (node (ref "C20") (pin "2") (pinfunction "2_2") (pintype "passive"))
      (node (ref "R19") (pin "1") (pinfunction "1_1") (pintype "passive"))
      (node (ref "U1") (pin "56") (pinfunction "PB4(NJTRST)_56") (pintype "bidirectional"))
      (node (ref "U4") (pin "3") (pinfunction "~{RESET}_3") (pintype "input"))
    )
    (net (code "45") (name "/MUX_SCL") (class "Default")
      (node (ref "R18") (pin "1") (pinfunction "1_1") (pintype "passive"))
      (node (ref "U1") (pin "58") (pinfunction "PB6_58") (pintype "bidirectional"))
      (node (ref "U4") (pin "22") (pinfunction "SCL_22") (pintype "bidirectional"))
    )
    (net (code "46") (name "/MUX_SDA") (class "Default")
      (node (ref "R17") (pin "1") (pinfunction "1_1") (pintype "passive"))
      (node (ref "U1") (pin "59") (pinfunction "PB7_59") (pintype "bidirectional"))
      (node (ref "U4") (pin "23") (pinfunction "SDA_23") (pintype "bidirectional"))
    )
    (net (code "47") (name "/PA15_GPIO") (class "Default")
      (node (ref "J14") (pin "5") (pinfunction "5_5") (pintype "passive"))
      (node (ref "U1") (pin "50") (pinfunction "PA15(JTDI)_50") (pintype "bidirectional"))
    )
    (net (code "48") (name "/PC10_GPIO") (class "Default")
      (node (ref "J14") (pin "2") (pinfunction "2_2") (pintype "passive"))
      (node (ref "U1") (pin "51") (pinfunction "PC10_51") (pintype "bidirectional"))
    )
    (net (code "49") (name "/PC11_GPIO") (class "Default")
      (node (ref "J14") (pin "3") (pinfunction "3_3") (pintype "passive"))
      (node (ref "U1") (pin "52") (pinfunction "PC11_52") (pintype "bidirectional"))
    )
    (net (code "50") (name "/PC12_GPIO") (class "Default")
      (node (ref "J14") (pin "4") (pinfunction "4_4") (pintype "passive"))
      (node (ref "U1") (pin "53") (pinfunction "PC12_53") (pintype "bidirectional"))
    )
    (net (code "51") (name "/PWR_LED_K") (class "Default")
      (node (ref "D2") (pin "2") (pinfunction "K_2") (pintype "passive"))
      (node (ref "R9") (pin "2") (pinfunction "2_2") (pintype "passive"))
    )
    (net (code "52") (name "/RM_ENC_CHA") (class "Default")
      (node (ref "J11") (pin "3") (pinfunction "3_3") (pintype "passive"))
      (node (ref "U1") (pin "41") (pinfunction "PA8_41") (pintype "bidirectional"))
    )
    (net (code "53") (name "/RM_ENC_CHB") (class "Default")
      (node (ref "J11") (pin "4") (pinfunction "4_4") (pintype "passive"))
      (node (ref "U1") (pin "42") (pinfunction "PA9_42") (pintype "bidirectional"))
    )
    (net (code "54") (name "/RM_N") (class "Default")
      (node (ref "J11") (pin "6") (pinfunction "6_6") (pintype "passive"))
      (node (ref "J12") (pin "6") (pinfunction "6_6") (pintype "passive"))
    )
    (net (code "55") (name "/RM_P") (class "Default")
      (node (ref "J11") (pin "1") (pinfunction "1_1") (pintype "passive"))
      (node (ref "J12") (pin "7") (pinfunction "7_7") (pintype "passive"))
    )
    (net (code "56") (name "/RM_PWM_INA") (class "Default")
      (node (ref "J13") (pin "6") (pinfunction "6_6") (pintype "passive"))
      (node (ref "U1") (pin "37") (pinfunction "PC6_37") (pintype "bidirectional"))
    )
    (net (code "57") (name "/RM_PWM_INB") (class "Default")
      (node (ref "J13") (pin "5") (pinfunction "5_5") (pintype "passive"))
      (node (ref "U1") (pin "38") (pinfunction "PC7_38") (pintype "bidirectional"))
    )
    (net (code "58") (name "/TOF_SC0") (class "Default")
      (node (ref "J4") (pin "3") (pinfunction "3_3") (pintype "passive"))
      (node (ref "U4") (pin "5") (pinfunction "SC0_5") (pintype "bidirectional"))
    )
    (net (code "59") (name "/TOF_SC1") (class "Default")
      (node (ref "J5") (pin "3") (pinfunction "3_3") (pintype "passive"))
      (node (ref "U4") (pin "7") (pinfunction "SC1_7") (pintype "bidirectional"))
    )
    (net (code "60") (name "/TOF_SC2") (class "Default")
      (node (ref "J6") (pin "3") (pinfunction "3_3") (pintype "passive"))
      (node (ref "U4") (pin "9") (pinfunction "SC2_9") (pintype "bidirectional"))
    )
    (net (code "61") (name "/TOF_SC3") (class "Default")
      (node (ref "J7") (pin "3") (pinfunction "3_3") (pintype "passive"))
      (node (ref "U4") (pin "11") (pinfunction "SC3_11") (pintype "bidirectional"))
    )
    (net (code "62") (name "/TOF_SC4") (class "Default")
      (node (ref "J8") (pin "3") (pinfunction "3_3") (pintype "passive"))
      (node (ref "U4") (pin "14") (pinfunction "SC4_14") (pintype "bidirectional"))
    )
    (net (code "63") (name "/TOF_SD0") (class "Default")
      (node (ref "J4") (pin "4") (pinfunction "4_4") (pintype "passive"))
      (node (ref "U4") (pin "4") (pinfunction "SD0_4") (pintype "bidirectional"))
    )
    (net (code "64") (name "/TOF_SD1") (class "Default")
      (node (ref "J5") (pin "4") (pinfunction "4_4") (pintype "passive"))
      (node (ref "U4") (pin "6") (pinfunction "SD1_6") (pintype "bidirectional"))
    )
    (net (code "65") (name "/TOF_SD2") (class "Default")
      (node (ref "J6") (pin "4") (pinfunction "4_4") (pintype "passive"))
      (node (ref "U4") (pin "8") (pinfunction "SD2_8") (pintype "bidirectional"))
    )
    (net (code "66") (name "/TOF_SD3") (class "Default")
      (node (ref "J7") (pin "4") (pinfunction "4_4") (pintype "passive"))
      (node (ref "U4") (pin "10") (pinfunction "SD3_10") (pintype "bidirectional"))
    )
    (net (code "67") (name "/TOF_SD4") (class "Default")
      (node (ref "J8") (pin "4") (pinfunction "4_4") (pintype "passive"))
      (node (ref "U4") (pin "13") (pinfunction "SD4_13") (pintype "bidirectional"))
    )
    (net (code "68") (name "/USB_CC1") (class "Default")
      (node (ref "J1") (pin "A5") (pinfunction "CC1_A5") (pintype "passive"))
      (node (ref "R2") (pin "2") (pinfunction "2_2") (pintype "passive"))
    )
    (net (code "69") (name "/USB_CC2") (class "Default")
      (node (ref "J1") (pin "B5") (pinfunction "CC2_B5") (pintype "passive"))
      (node (ref "R1") (pin "2") (pinfunction "2_2") (pintype "passive"))
    )
    (net (code "70") (name "/USB_D_N") (class "Default")
      (node (ref "D1") (pin "6") (pinfunction "IO1_6") (pintype "bidirectional"))
      (node (ref "U1") (pin "44") (pinfunction "PA11_44") (pintype "bidirectional"))
    )
    (net (code "71") (name "/USB_D_P") (class "Default")
      (node (ref "D1") (pin "4") (pinfunction "IO2_4") (pintype "bidirectional"))
      (node (ref "U1") (pin "45") (pinfunction "PA12_45") (pintype "bidirectional"))
    )
    (net (code "72") (name "/XTAL_IN") (class "Default")
      (node (ref "C4") (pin "2") (pinfunction "2_2") (pintype "passive"))
      (node (ref "R8") (pin "2") (pinfunction "2_2") (pintype "passive"))
      (node (ref "X1") (pin "1") (pinfunction "1_1") (pintype "passive"))
    )
    (net (code "73") (name "GND") (class "Default")
      (node (ref "C1") (pin "1") (pinfunction "1_1") (pintype "passive"))
      (node (ref "C10") (pin "1") (pinfunction "1_1") (pintype "passive"))
      (node (ref "C11") (pin "1") (pinfunction "1_1") (pintype "passive"))
      (node (ref "C12") (pin "1") (pinfunction "1_1") (pintype "passive"))
      (node (ref "C13") (pin "1") (pinfunction "1_1") (pintype "passive"))
      (node (ref "C14") (pin "2") (pinfunction "2_2") (pintype "passive"))
      (node (ref "C15") (pin "1") (pinfunction "1_1") (pintype "passive"))
      (node (ref "C16") (pin "2") (pinfunction "2_2") (pintype "passive"))
      (node (ref "C17") (pin "1") (pinfunction "1_1") (pintype "passive"))
      (node (ref "C18") (pin "2") (pinfunction "2_2") (pintype "passive"))
      (node (ref "C19") (pin "1") (pinfunction "1_1") (pintype "passive"))
      (node (ref "C2") (pin "2") (pinfunction "2_2") (pintype "passive"))
      (node (ref "C20") (pin "1") (pinfunction "1_1") (pintype "passive"))
      (node (ref "C21") (pin "1") (pinfunction "1_1") (pintype "passive"))
      (node (ref "C22") (pin "2") (pinfunction "2_2") (pintype "passive"))
      (node (ref "C3") (pin "2") (pinfunction "2_2") (pintype "passive"))
      (node (ref "C4") (pin "1") (pinfunction "1_1") (pintype "passive"))
      (node (ref "C5") (pin "1") (pinfunction "1_1") (pintype "passive"))
      (node (ref "C6") (pin "1") (pinfunction "1_1") (pintype "passive"))
      (node (ref "C7") (pin "2") (pinfunction "2_2") (pintype "passive"))
      (node (ref "C8") (pin "2") (pinfunction "2_2") (pintype "passive"))
      (node (ref "C9") (pin "1") (pinfunction "1_1") (pintype "passive"))
      (node (ref "D1") (pin "2") (pinfunction "GND_2") (pintype "power_in"))
      (node (ref "J1") (pin "A1B12") (pinfunction "GND_A1B12_A1B12") (pintype "passive"))
      (node (ref "J1") (pin "B1A12") (pinfunction "GND_B1A12_B1A12") (pintype "passive"))
      (node (ref "J1") (pin "S1") (pinfunction "SHIELD_1_S1") (pintype "passive"))
      (node (ref "J1") (pin "S2") (pinfunction "SHIELD_2_S2") (pintype "passive"))
      (node (ref "J1") (pin "S3") (pinfunction "SHIELD_3_S3") (pintype "passive"))
      (node (ref "J1") (pin "S4") (pinfunction "SHIELD_4_S4") (pintype "passive"))
      (node (ref "J10") (pin "5") (pinfunction "5_5") (pintype "passive"))
      (node (ref "J11") (pin "5") (pinfunction "5_5") (pintype "passive"))
      (node (ref "J12") (pin "3") (pinfunction "3_3") (pintype "passive"))
      (node (ref "J12") (pin "8") (pinfunction "8_8") (pintype "passive"))
      (node (ref "J13") (pin "8") (pinfunction "8_8") (pintype "passive"))
      (node (ref "J14") (pin "6") (pinfunction "6_6") (pintype "passive"))
      (node (ref "J2") (pin "3") (pinfunction "3_3") (pintype "passive"))
      (node (ref "J3") (pin "6") (pinfunction "6_6") (pintype "passive"))
      (node (ref "J4") (pin "2") (pinfunction "2_2") (pintype "passive"))
      (node (ref "J5") (pin "2") (pinfunction "2_2") (pintype "passive"))
      (node (ref "J6") (pin "2") (pinfunction "2_2") (pintype "passive"))
      (node (ref "J7") (pin "2") (pinfunction "2_2") (pintype "passive"))
      (node (ref "J8") (pin "2") (pinfunction "2_2") (pintype "passive"))
      (node (ref "J9") (pin "4") (pinfunction "4_4") (pintype "passive"))
      (node (ref "R1") (pin "1") (pinfunction "1_1") (pintype "passive"))
      (node (ref "R10") (pin "1") (pinfunction "1_1") (pintype "passive"))
      (node (ref "R2") (pin "1") (pinfunction "1_1") (pintype "passive"))
      (node (ref "R3") (pin "1") (pinfunction "1_1") (pintype "passive"))
      (node (ref "R4") (pin "1") (pinfunction "1_1") (pintype "passive"))
      (node (ref "R5") (pin "1") (pinfunction "1_1") (pintype "passive"))
      (node (ref "R9") (pin "1") (pinfunction "1_1") (pintype "passive"))
      (node (ref "S2") (pin "3") (pinfunction "3_3") (pintype "passive"))
      (node (ref "S3") (pin "3") (pinfunction "3_3") (pintype "passive"))
      (node (ref "S5") (pin "3") (pinfunction "3_3") (pintype "passive"))
      (node (ref "S6") (pin "3") (pinfunction "3_3") (pintype "passive"))
      (node (ref "S6") (pin "4") (pinfunction "4_4") (pintype "passive"))
      (node (ref "S7") (pin "3") (pinfunction "3_3") (pintype "passive"))
      (node (ref "U1") (pin "12") (pinfunction "VSSA_12") (pintype "power_in"))
      (node (ref "U1") (pin "18") (pinfunction "VSS_18") (pintype "power_in"))
      (node (ref "U1") (pin "63") (pinfunction "VSS_63") (pintype "power_in"))
      (node (ref "U2") (pin "1") (pinfunction "GND_1") (pintype "power_in"))
      (node (ref "U3") (pin "10") (pinfunction "RESV_10_10") (pintype "passive"))
      (node (ref "U3") (pin "11") (pinfunction "RESV_11_11") (pintype "passive"))
      (node (ref "U3") (pin "2") (pinfunction "RESV_2_2") (pintype "passive"))
      (node (ref "U3") (pin "3") (pinfunction "RESV_3_3") (pintype "passive"))
      (node (ref "U3") (pin "6") (pinfunction "GND_6") (pintype "power_in"))
      (node (ref "U3") (pin "7") (pinfunction "RESV_7_7") (pintype "passive"))
      (node (ref "U3") (pin "9") (pinfunction "INT2/FSYNC/CLKIN_9") (pintype "passive"))
      (node (ref "U4") (pin "1") (pinfunction "A0_1") (pintype "input"))
      (node (ref "U4") (pin "12") (pinfunction "GND_12") (pintype "power_in"))
      (node (ref "U4") (pin "2") (pinfunction "A1_2") (pintype "input"))
      (node (ref "U4") (pin "21") (pinfunction "A2_21") (pintype "input"))
      (node (ref "X1") (pin "2") (pinfunction "2_2") (pintype "passive"))
      (node (ref "X1") (pin "4") (pinfunction "4_4") (pintype "passive"))
    )
    (net (code "74") (name "unconnected-(J1-SBU1-PadA8)") (class "Default")
      (node (ref "J1") (pin "A8") (pinfunction "SBU1_A8") (pintype "passive+no_connect"))
    )
    (net (code "75") (name "unconnected-(J1-SBU2-PadB8)") (class "Default")
      (node (ref "J1") (pin "B8") (pinfunction "SBU2_B8") (pintype "passive+no_connect"))
    )
    (net (code "76") (name "unconnected-(J12-Pad2)") (class "Default")
      (node (ref "J12") (pin "2") (pinfunction "2_2") (pintype "passive+no_connect"))
    )
    (net (code "77") (name "unconnected-(J13-Pad1)") (class "Default")
      (node (ref "J13") (pin "1") (pinfunction "1_1") (pintype "passive+no_connect"))
    )
    (net (code "78") (name "unconnected-(J13-Pad7)") (class "Default")
      (node (ref "J13") (pin "7") (pinfunction "7_7") (pintype "passive+no_connect"))
    )
    (net (code "79") (name "unconnected-(U1A-PA2-Pad16)") (class "Default")
      (node (ref "U1") (pin "16") (pinfunction "PA2_16") (pintype "bidirectional+no_connect"))
    )
    (net (code "80") (name "unconnected-(U1A-PA3-Pad17)") (class "Default")
      (node (ref "U1") (pin "17") (pinfunction "PA3_17") (pintype "bidirectional+no_connect"))
    )
    (net (code "81") (name "unconnected-(U1A-PA10-Pad43)") (class "Default")
      (node (ref "U1") (pin "43") (pinfunction "PA10_43") (pintype "bidirectional+no_connect"))
    )
    (net (code "82") (name "unconnected-(U1A-PB1-Pad27)") (class "Default")
      (node (ref "U1") (pin "27") (pinfunction "PB1_27") (pintype "bidirectional+no_connect"))
    )
    (net (code "83") (name "unconnected-(U1A-PB5-Pad57)") (class "Default")
      (node (ref "U1") (pin "57") (pinfunction "PB5_57") (pintype "bidirectional+no_connect"))
    )
    (net (code "84") (name "unconnected-(U1A-PB8-Pad61)") (class "Default")
      (node (ref "U1") (pin "61") (pinfunction "PB8_61") (pintype "bidirectional+no_connect"))
    )
    (net (code "85") (name "unconnected-(U1A-PB9-Pad62)") (class "Default")
      (node (ref "U1") (pin "62") (pinfunction "PB9_62") (pintype "bidirectional+no_connect"))
    )
    (net (code "86") (name "unconnected-(U1A-PB12-Pad33)") (class "Default")
      (node (ref "U1") (pin "33") (pinfunction "PB12_33") (pintype "bidirectional+no_connect"))
    )
    (net (code "87") (name "unconnected-(U1A-PB13-Pad34)") (class "Default")
      (node (ref "U1") (pin "34") (pinfunction "PB13_34") (pintype "bidirectional+no_connect"))
    )
    (net (code "88") (name "unconnected-(U1A-PB15-Pad36)") (class "Default")
      (node (ref "U1") (pin "36") (pinfunction "PB15_36") (pintype "bidirectional+no_connect"))
    )
    (net (code "89") (name "unconnected-(U1A-PC4-Pad24)") (class "Default")
      (node (ref "U1") (pin "24") (pinfunction "PC4_24") (pintype "bidirectional+no_connect"))
    )
    (net (code "90") (name "unconnected-(U1A-PC5-Pad25)") (class "Default")
      (node (ref "U1") (pin "25") (pinfunction "PC5_25") (pintype "bidirectional+no_connect"))
    )
    (net (code "91") (name "unconnected-(U1A-PC13-Pad2)") (class "Default")
      (node (ref "U1") (pin "2") (pinfunction "PC13_2") (pintype "bidirectional+no_connect"))
    )
    (net (code "92") (name "unconnected-(U1A-PC14-OSC32_IN(PC14)-Pad3)") (class "Default")
      (node (ref "U1") (pin "3") (pinfunction "PC14-OSC32_IN(PC14)_3") (pintype "bidirectional+no_connect"))
    )
    (net (code "93") (name "unconnected-(U1A-PC15-OSC32_OUT(PC15)-Pad4)") (class "Default")
      (node (ref "U1") (pin "4") (pinfunction "PC15-OSC32_OUT(PC15)_4") (pintype "bidirectional+no_connect"))
    )
    (net (code "94") (name "unconnected-(U1A-PD2-Pad54)") (class "Default")
      (node (ref "U1") (pin "54") (pinfunction "PD2_54") (pintype "bidirectional+no_connect"))
    )
    (net (code "95") (name "unconnected-(U4-SC5-Pad16)") (class "Default")
      (node (ref "U4") (pin "16") (pinfunction "SC5_16") (pintype "bidirectional+no_connect"))
    )
    (net (code "96") (name "unconnected-(U4-SC6-Pad18)") (class "Default")
      (node (ref "U4") (pin "18") (pinfunction "SC6_18") (pintype "bidirectional+no_connect"))
    )
    (net (code "97") (name "unconnected-(U4-SC7-Pad20)") (class "Default")
      (node (ref "U4") (pin "20") (pinfunction "SC7_20") (pintype "bidirectional+no_connect"))
    )
    (net (code "98") (name "unconnected-(U4-SD5-Pad15)") (class "Default")
      (node (ref "U4") (pin "15") (pinfunction "SD5_15") (pintype "bidirectional+no_connect"))
    )
    (net (code "99") (name "unconnected-(U4-SD6-Pad17)") (class "Default")
      (node (ref "U4") (pin "17") (pinfunction "SD6_17") (pintype "bidirectional+no_connect"))
    )
    (net (code "100") (name "unconnected-(U4-SD7-Pad19)") (class "Default")
      (node (ref "U4") (pin "19") (pinfunction "SD7_19") (pintype "bidirectional+no_connect"))
    )
  )
)
